# design.net
KiCad netlist of a schematic drawn in Altium Designer
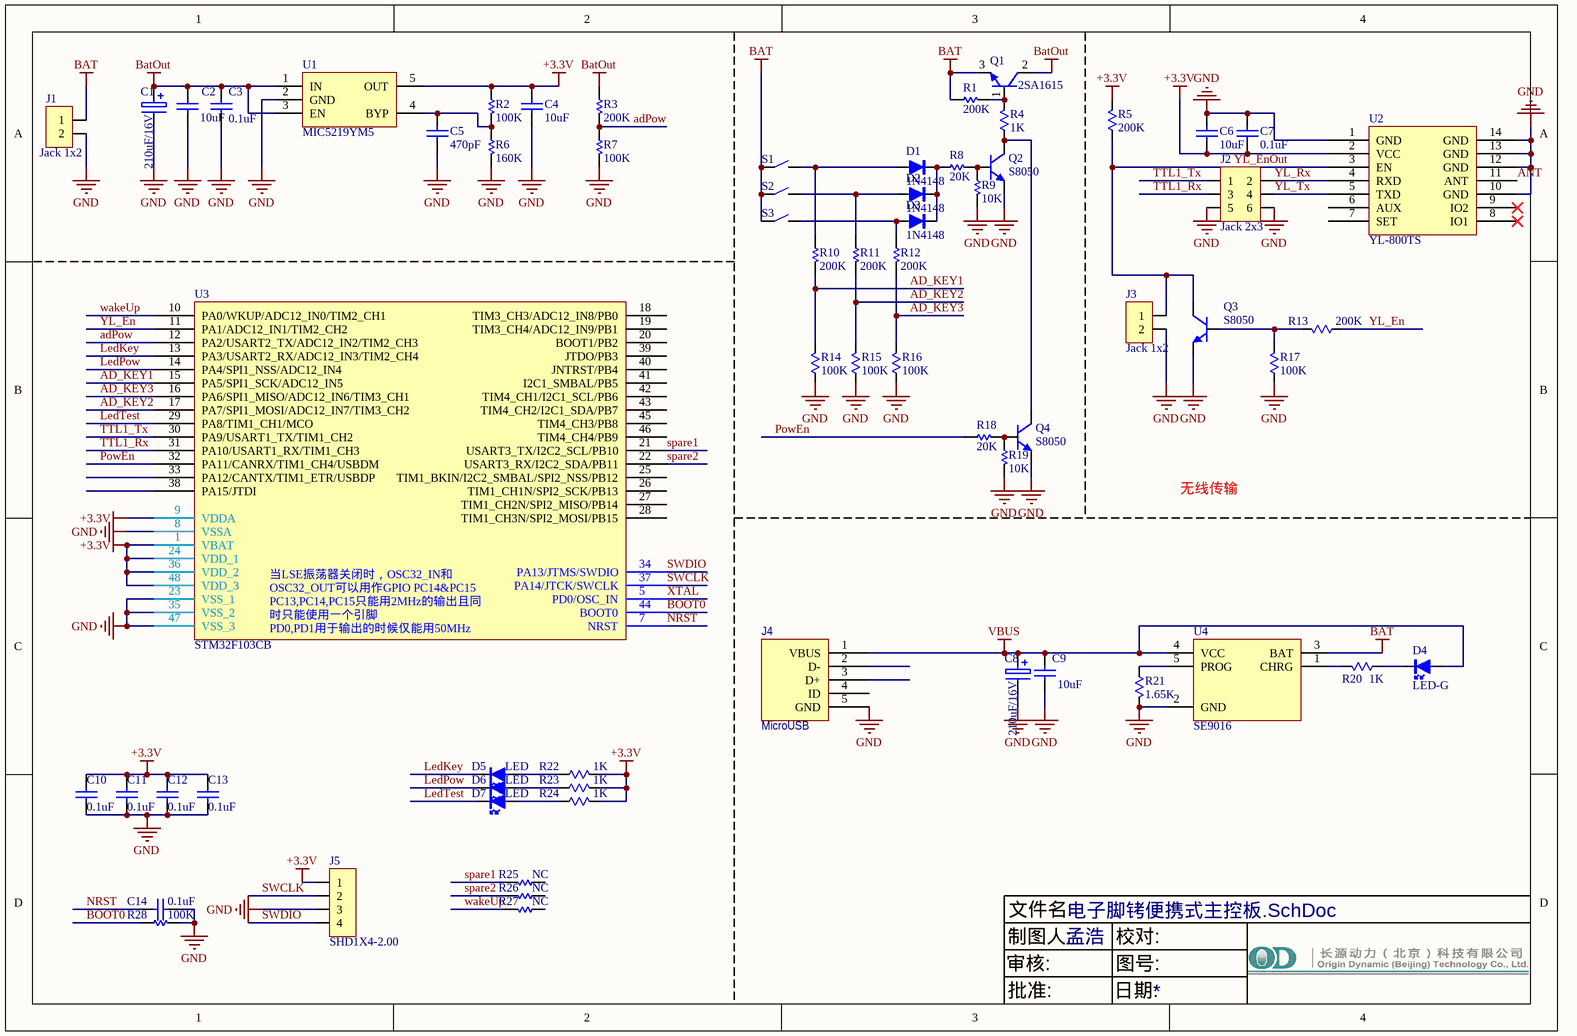
[diagram p0: 电子脚铐便携式主控板.SchDoc]

(export (version "E")
  (design (tool "Eeschema 10.0.6"))
  (components
    (comp (ref "C1") (value "210uF/16V") (footprint "C7343") (libsource (lib "RLCYDF") (part "Cap Poll")))
    (comp (ref "C2")
      (value "10uF")
      (footprint "C0603")
      (description "CAP")
      (fields (field (name "PUBLISHER") "Altium Limited"))
      (libsource (lib "Passive Components Class") (part "CAP"))
    )
    (comp (ref "C3") (value "0.1uF") (footprint "C0603") (libsource (lib "RLCYDF") (part "Cap Semi")))
    (comp (ref "C4")
      (value "10uF")
      (footprint "C0603")
      (description "CAP")
      (fields (field (name "PUBLISHER") "Altium Limited"))
      (libsource (lib "Passive Components Class") (part "CAP"))
    )
    (comp (ref "C5")
      (value "470pF")
      (footprint "C0603")
      (description "CAP")
      (fields (field (name "PUBLISHER") "Altium Limited"))
      (libsource (lib "Passive Components Class") (part "CAP"))
    )
    (comp (ref "C6")
      (value "10uF")
      (footprint "C0603")
      (description "CAP")
      (fields (field (name "PUBLISHER") "Altium Limited"))
      (libsource (lib "Passive Components Class") (part "CAP"))
    )
    (comp (ref "C7")
      (value "0.1uF")
      (footprint "C0603")
      (description "CAP")
      (fields (field (name "PUBLISHER") "Altium Limited"))
      (libsource (lib "Passive Components Class") (part "CAP"))
    )
    (comp (ref "C8") (value "210uF/16V") (footprint "C7343") (libsource (lib "RLCYDF") (part "Cap Poll")))
    (comp (ref "C9")
      (value "10uF")
      (footprint "C0603")
      (description "Capacitor")
      (fields (field (name "Comment") "Cap") (field (name "PUBLISHER") "Altium Limited"))
      (libsource (lib "Miscellaneous Devices") (part "Cap"))
    )
    (comp (ref "C10") (value "0.1uF") (footprint "C0603") (libsource (lib "RLCYDF") (part "Cap Semi")))
    (comp (ref "C11") (value "0.1uF") (footprint "C0603") (libsource (lib "RLCYDF") (part "Cap Semi")))
    (comp (ref "C12") (value "0.1uF") (footprint "C0603") (libsource (lib "RLCYDF") (part "Cap Semi")))
    (comp (ref "C13") (value "0.1uF") (footprint "C0603") (libsource (lib "RLCYDF") (part "Cap Semi")))
    (comp (ref "C14") (value "0.1uF") (footprint "C0603") (libsource (lib "RLCYDF") (part "Cap Semi")))
    (comp (ref "D1")
      (value "1N4148")
      (footprint "SOD-80-S")
      (description "Silicon Epitaxial Planar Diodes")
      (libsource (lib "Passive Components Class") (part "DIODE-SWITCHING"))
    )
    (comp (ref "D2")
      (value "1N4148")
      (footprint "SOD-80-S")
      (description "Silicon Epitaxial Planar Diodes")
      (libsource (lib "Passive Components Class") (part "DIODE-SWITCHING"))
    )
    (comp (ref "D3")
      (value "1N4148")
      (footprint "SOD-80-S")
      (description "Silicon Epitaxial Planar Diodes")
      (libsource (lib "Passive Components Class") (part "DIODE-SWITCHING"))
    )
    (comp (ref "D4")
      (value "LED-G")
      (footprint "LED0805")
      (libsource (lib "Passive Components Class") (part "LED"))
    )
    (comp (ref "D5")
      (value "LED")
      (footprint "LED0805")
      (libsource (lib "Passive Components Class") (part "LED"))
    )
    (comp (ref "D6")
      (value "LED")
      (footprint "LED0805")
      (libsource (lib "Passive Components Class") (part "LED"))
    )
    (comp (ref "D7")
      (value "LED")
      (footprint "LED0805")
      (libsource (lib "Passive Components Class") (part "LED"))
    )
    (comp (ref "J1")
      (value "Jack 1x2")
      (footprint "DF13-2P-1.25V")
      (description "插座")
      (libsource (lib "Connector") (part "Jack 1x2"))
    )
    (comp (ref "J2")
      (value "Jack 2x3")
      (footprint "Jk2*3-2.0")
      (description "双排座")
      (libsource (lib "Connector") (part "Jack 2x3"))
    )
    (comp (ref "J3")
      (value "Jack 1x2")
      (footprint "A6S-1101-PH")
      (description "插座")
      (libsource (lib "Connector") (part "Jack 1x2"))
    )
    (comp (ref "J4") (value "MicroUSB") (footprint "MICRO-USB") (libsource (lib "JLib") (part "MicroUSB")))
    (comp (ref "J5")
      (value "SHD1X4-2.00")
      (footprint "Jk1*4-2.0")
      (libsource (lib "Connector Class") (part "HEADER1X4"))
    )
    (comp (ref "Q1") (value "2SA1615") (footprint "TO-252") (libsource (lib "ArmArmor") (part "MJD122")))
    (comp (ref "Q2")
      (value "S8050")
      (footprint "SOT-23")
      (description "NPN triode, 0.5A Max")
      (libsource (lib "RLCYDF") (part "S8050"))
    )
    (comp (ref "Q3")
      (value "S8050")
      (footprint "SOT-23")
      (description "NPN triode, 0.5A Max")
      (libsource (lib "RLCYDF") (part "S8050"))
    )
    (comp (ref "Q4")
      (value "S8050")
      (footprint "SOT-23")
      (description "NPN triode, 0.5A Max")
      (libsource (lib "RLCYDF") (part "S8050"))
    )
    (comp (ref "R1") (value "200K") (footprint "R0603") (libsource (lib "RLCYDF") (part "Res")))
    (comp (ref "R2") (value "100K") (footprint "R0603") (libsource (lib "RLCYDF") (part "Res")))
    (comp (ref "R3") (value "200K") (footprint "R0603") (libsource (lib "RLCYDF") (part "Res")))
    (comp (ref "R4")
      (value "1K")
      (footprint "R0603")
      (description "Resistor")
      (fields (field (name "PUBLISHER") "Altium Limited"))
      (libsource (lib "Passive Components Class") (part "RES"))
    )
    (comp (ref "R5")
      (value "200K")
      (footprint "R0603")
      (description "Resistor")
      (fields (field (name "PUBLISHER") "Altium Limited"))
      (libsource (lib "Passive Components Class") (part "RES"))
    )
    (comp (ref "R6") (value "160K") (footprint "R0603") (libsource (lib "RLCYDF") (part "Res")))
    (comp (ref "R7") (value "100K") (footprint "R0603") (libsource (lib "RLCYDF") (part "Res")))
    (comp (ref "R8") (value "20K") (footprint "R0603") (libsource (lib "RLCYDF") (part "Res")))
    (comp (ref "R9") (value "10K") (footprint "R0603") (libsource (lib "RLCYDF") (part "Res")))
    (comp (ref "R10") (value "200K") (footprint "R0603") (libsource (lib "RLCYDF") (part "Res")))
    (comp (ref "R11") (value "200K") (footprint "R0603") (libsource (lib "RLCYDF") (part "Res")))
    (comp (ref "R12") (value "200K") (footprint "R0603") (libsource (lib "RLCYDF") (part "Res")))
    (comp (ref "R13")
      (value "200K")
      (footprint "R0603")
      (description "Resistor")
      (fields (field (name "PUBLISHER") "Altium Limited"))
      (libsource (lib "Passive Components Class") (part "RES"))
    )
    (comp (ref "R14")
      (value "100K")
      (footprint "R0603")
      (description "Resistor")
      (fields (field (name "PUBLISHER") "Altium Limited"))
      (libsource (lib "Passive Components Class") (part "RES"))
    )
    (comp (ref "R15")
      (value "100K")
      (footprint "R0603")
      (description "Resistor")
      (fields (field (name "PUBLISHER") "Altium Limited"))
      (libsource (lib "Passive Components Class") (part "RES"))
    )
    (comp (ref "R16")
      (value "100K")
      (footprint "R0603")
      (description "Resistor")
      (fields (field (name "PUBLISHER") "Altium Limited"))
      (libsource (lib "Passive Components Class") (part "RES"))
    )
    (comp (ref "R17")
      (value "100K")
      (footprint "R0603")
      (description "Resistor")
      (fields (field (name "PUBLISHER") "Altium Limited"))
      (libsource (lib "Passive Components Class") (part "RES"))
    )
    (comp (ref "R18") (value "20K") (footprint "R0603") (libsource (lib "RLCYDF") (part "Res")))
    (comp (ref "R19") (value "10K") (footprint "R0603") (libsource (lib "RLCYDF") (part "Res")))
    (comp (ref "R20")
      (value "1K")
      (footprint "R0603")
      (description "Resistor")
      (fields (field (name "PUBLISHER") "Altium Limited"))
      (libsource (lib "UP-Robot") (part "Res"))
    )
    (comp (ref "R21")
      (value "1.65K")
      (footprint "R0603")
      (description "Resistor")
      (fields (field (name "PUBLISHER") "Altium Limited"))
      (libsource (lib "Temp") (part "Res"))
    )
    (comp (ref "R22")
      (value "1K")
      (footprint "R0603")
      (description "Resistor")
      (fields (field (name "PUBLISHER") "Altium Limited"))
      (libsource (lib "UP-Robot") (part "Res"))
    )
    (comp (ref "R23")
      (value "1K")
      (footprint "R0603")
      (description "Resistor")
      (fields (field (name "PUBLISHER") "Altium Limited"))
      (libsource (lib "UP-Robot") (part "Res"))
    )
    (comp (ref "R24")
      (value "1K")
      (footprint "R0603")
      (description "Resistor")
      (fields (field (name "PUBLISHER") "Altium Limited"))
      (libsource (lib "UP-Robot") (part "Res"))
    )
    (comp (ref "R25") (value "NC") (footprint "R0603") (libsource (lib "RLCYDF") (part "Res")))
    (comp (ref "R26") (value "NC") (footprint "R0603") (libsource (lib "RLCYDF") (part "Res")))
    (comp (ref "R27") (value "NC") (footprint "R0603") (libsource (lib "RLCYDF") (part "Res")))
    (comp (ref "R28") (value "100K") (footprint "R0603") (libsource (lib "RLCYDF") (part "Res")))
    (comp (ref "S1") (value "Switch") (footprint "B3F-4055") (libsource (lib "Connector") (part "Sw")))
    (comp (ref "S2") (value "Switch") (footprint "B3F-4055") (libsource (lib "Connector") (part "Sw")))
    (comp (ref "S3") (value "Switch") (footprint "B3F-4055") (libsource (lib "Connector") (part "Sw")))
    (comp (ref "U1") (value "MIC5219YM5") (footprint "SOT-23-5") (libsource (lib "Power") (part "MIC5205")))
    (comp (ref "U2") (value "YL-800TS") (footprint "YL-800TS") (libsource (lib "Module") (part "YL-800TS")))
    (comp (ref "U3")
      (value "STM32F103CB")
      (footprint "LQFP48")
      (libsource (lib "stm32") (part "STM32F103Cx"))
    )
    (comp (ref "U4") (value "SE9016") (footprint "SOT-23-5") (libsource (lib "chip") (part "SE9016")))
  )
  (nets
    (net (code "1") (name "+3.3V") (class "Default")
      (node (ref "C10") (pin "1") (pinfunction "1_1") (pintype "passive"))
      (node (ref "C11") (pin "1") (pinfunction "1_1") (pintype "passive"))
      (node (ref "C12") (pin "1") (pinfunction "1_1") (pintype "passive"))
      (node (ref "C13") (pin "1") (pinfunction "1_1") (pintype "passive"))
      (node (ref "C4") (pin "1") (pinfunction "1_1") (pintype "passive"))
      (node (ref "C6") (pin "1") (pinfunction "1_1") (pintype "passive"))
      (node (ref "C7") (pin "1") (pinfunction "1_1") (pintype "passive"))
      (node (ref "J5") (pin "1") (pinfunction "1_1") (pintype "passive"))
      (node (ref "R2") (pin "1") (pinfunction "1_1") (pintype "passive"))
      (node (ref "R22") (pin "1") (pinfunction "1_1") (pintype "passive"))
      (node (ref "R23") (pin "1") (pinfunction "1_1") (pintype "passive"))
      (node (ref "R24") (pin "1") (pinfunction "1_1") (pintype "passive"))
      (node (ref "R5") (pin "2") (pinfunction "2_2") (pintype "passive"))
      (node (ref "U1") (pin "5") (pinfunction "OUT_5") (pintype "passive"))
      (node (ref "U2") (pin "2") (pinfunction "VCC_2") (pintype "passive"))
      (node (ref "U3") (pin "1") (pinfunction "VBAT_1") (pintype "power_in"))
      (node (ref "U3") (pin "24") (pinfunction "VDD_1_24") (pintype "power_in"))
      (node (ref "U3") (pin "36") (pinfunction "VDD_2_36") (pintype "power_in"))
      (node (ref "U3") (pin "48") (pinfunction "VDD_3_48") (pintype "power_in"))
      (node (ref "U3") (pin "9") (pinfunction "VDDA_9") (pintype "power_in"))
    )
    (net (code "2") (name "/AD_KEY1") (class "Default")
      (node (ref "R10") (pin "2") (pinfunction "2_2") (pintype "passive"))
      (node (ref "R14") (pin "2") (pinfunction "2_2") (pintype "passive"))
      (node (ref "U3") (pin "15") (pinfunction "PA5/SPI1_SCK/ADC12_IN5_15") (pintype "passive"))
    )
    (net (code "3") (name "/AD_KEY2") (class "Default")
      (node (ref "R11") (pin "2") (pinfunction "2_2") (pintype "passive"))
      (node (ref "R15") (pin "2") (pinfunction "2_2") (pintype "passive"))
      (node (ref "U3") (pin "17") (pinfunction "PA7/SPI1_MOSI/ADC12_IN7/TIM3_CH2_17") (pintype "passive"))
    )
    (net (code "4") (name "/AD_KEY3") (class "Default")
      (node (ref "R12") (pin "2") (pinfunction "2_2") (pintype "passive"))
      (node (ref "R16") (pin "2") (pinfunction "2_2") (pintype "passive"))
      (node (ref "U3") (pin "16") (pinfunction "PA6/SPI1_MISO/ADC12_IN6/TIM3_CH1_16") (pintype "passive"))
    )
    (net (code "5") (name "/ANT") (class "Default")
      (node (ref "U2") (pin "11") (pinfunction "ANT_11") (pintype "passive"))
    )
    (net (code "6") (name "/BOOT0") (class "Default")
      (node (ref "R28") (pin "1") (pinfunction "1_1") (pintype "passive"))
      (node (ref "U3") (pin "44") (pinfunction "BOOT0_44") (pintype "passive"))
    )
    (net (code "7") (name "/LedKey") (class "Default")
      (node (ref "D5") (pin "2") (pinfunction "K_2") (pintype "passive"))
      (node (ref "U3") (pin "13") (pinfunction "PA3/USART2_RX/ADC12_IN3/TIM2_CH4_13") (pintype "passive"))
    )
    (net (code "8") (name "/LedPow") (class "Default")
      (node (ref "D6") (pin "2") (pinfunction "K_2") (pintype "passive"))
      (node (ref "U3") (pin "14") (pinfunction "PA4/SPI1_NSS/ADC12_IN4_14") (pintype "passive"))
    )
    (net (code "9") (name "/LedTest") (class "Default")
      (node (ref "D7") (pin "2") (pinfunction "K_2") (pintype "passive"))
      (node (ref "U3") (pin "29") (pinfunction "PA8/TIM1_CH1/MCO_29") (pintype "passive"))
    )
    (net (code "10") (name "/NRST") (class "Default")
      (node (ref "C14") (pin "1") (pinfunction "1_1") (pintype "passive"))
      (node (ref "U3") (pin "7") (pinfunction "NRST_7") (pintype "passive"))
    )
    (net (code "11") (name "/PowEn") (class "Default")
      (node (ref "R18") (pin "1") (pinfunction "1_1") (pintype "passive"))
      (node (ref "U3") (pin "32") (pinfunction "PA11/CANRX/TIM1_CH4/USBDM_32") (pintype "passive"))
    )
    (net (code "12") (name "/SWCLK") (class "Default")
      (node (ref "J5") (pin "2") (pinfunction "2_2") (pintype "passive"))
      (node (ref "U3") (pin "37") (pinfunction "PA14/JTCK/SWCLK_37") (pintype "passive"))
    )
    (net (code "13") (name "/SWDIO") (class "Default")
      (node (ref "J5") (pin "4") (pinfunction "4_4") (pintype "passive"))
      (node (ref "U3") (pin "34") (pinfunction "PA13/JTMS/SWDIO_34") (pintype "passive"))
    )
    (net (code "14") (name "/TTL1_Rx") (class "Default")
      (node (ref "J2") (pin "3") (pinfunction "3_3") (pintype "passive"))
      (node (ref "U3") (pin "31") (pinfunction "PA10/USART1_RX/TIM1_CH3_31") (pintype "passive"))
    )
    (net (code "15") (name "/TTL1_Tx") (class "Default")
      (node (ref "J2") (pin "1") (pinfunction "1_1") (pintype "passive"))
      (node (ref "U3") (pin "30") (pinfunction "PA9/USART1_TX/TIM1_CH2_30") (pintype "passive"))
    )
    (net (code "16") (name "/XTAL") (class "Default")
      (node (ref "U3") (pin "5") (pinfunction "PD0/OSC_IN_5") (pintype "passive"))
    )
    (net (code "17") (name "/YL_En") (class "Default")
      (node (ref "R13") (pin "1") (pinfunction "1_1") (pintype "passive"))
      (node (ref "U3") (pin "11") (pinfunction "PA1/ADC12_IN1/TIM2_CH2_11") (pintype "passive"))
    )
    (net (code "18") (name "/YL_EnOut") (class "Default")
      (node (ref "J3") (pin "1") (pinfunction "1_1") (pintype "passive"))
      (node (ref "Q3") (pin "3") (pinfunction "c_3") (pintype "passive"))
      (node (ref "R5") (pin "1") (pinfunction "1_1") (pintype "passive"))
      (node (ref "U2") (pin "3") (pinfunction "EN_3") (pintype "passive"))
    )
    (net (code "19") (name "/YL_Rx") (class "Default")
      (node (ref "J2") (pin "2") (pinfunction "2_2") (pintype "passive"))
      (node (ref "U2") (pin "4") (pinfunction "RXD_4") (pintype "passive"))
    )
    (net (code "20") (name "/YL_Tx") (class "Default")
      (node (ref "J2") (pin "4") (pinfunction "4_4") (pintype "passive"))
      (node (ref "U2") (pin "5") (pinfunction "TXD_5") (pintype "passive"))
    )
    (net (code "21") (name "/adPow") (class "Default")
      (node (ref "R3") (pin "2") (pinfunction "2_2") (pintype "passive"))
      (node (ref "R7") (pin "1") (pinfunction "1_1") (pintype "passive"))
      (node (ref "U3") (pin "12") (pinfunction "PA2/USART2_TX/ADC12_IN2/TIM2_CH3_12") (pintype "passive"))
    )
    (net (code "22") (name "/spare1") (class "Default")
      (node (ref "R25") (pin "2") (pinfunction "2_2") (pintype "passive"))
      (node (ref "U3") (pin "21") (pinfunction "USART3_TX/I2C2_SCL/PB10_21") (pintype "passive"))
    )
    (net (code "23") (name "/spare2") (class "Default")
      (node (ref "R26") (pin "2") (pinfunction "2_2") (pintype "passive"))
      (node (ref "U3") (pin "22") (pinfunction "USART3_RX/I2C2_SDA/PB11_22") (pintype "passive"))
    )
    (net (code "24") (name "/wakeUp") (class "Default")
      (node (ref "R27") (pin "2") (pinfunction "2_2") (pintype "passive"))
      (node (ref "U3") (pin "10") (pinfunction "PA0/WKUP/ADC12_IN0/TIM2_CH1_10") (pintype "passive"))
    )
    (net (code "25") (name "BAT") (class "Default")
      (node (ref "J1") (pin "1") (pinfunction "1_1") (pintype "passive"))
      (node (ref "Q1") (pin "3") (pinfunction "E_3") (pintype "passive"))
      (node (ref "R1") (pin "1") (pinfunction "1_1") (pintype "passive"))
      (node (ref "S1") (pin "1") (pinfunction "1_1") (pintype "passive"))
      (node (ref "S2") (pin "1") (pinfunction "1_1") (pintype "passive"))
      (node (ref "S3") (pin "1") (pinfunction "1_1") (pintype "passive"))
      (node (ref "U4") (pin "3") (pinfunction "BAT_3") (pintype "passive"))
    )
    (net (code "26") (name "BatOut") (class "Default")
      (node (ref "C1") (pin "1") (pinfunction "1_1") (pintype "passive"))
      (node (ref "C2") (pin "1") (pinfunction "1_1") (pintype "passive"))
      (node (ref "C3") (pin "2") (pinfunction "2_2") (pintype "passive"))
      (node (ref "Q1") (pin "2") (pinfunction "C_2") (pintype "passive"))
      (node (ref "R3") (pin "1") (pinfunction "1_1") (pintype "passive"))
      (node (ref "U1") (pin "1") (pinfunction "IN_1") (pintype "passive"))
      (node (ref "U1") (pin "3") (pinfunction "EN_3") (pintype "passive"))
    )
    (net (code "27") (name "GND") (class "Default")
      (node (ref "C1") (pin "2") (pinfunction "2_2") (pintype "passive"))
      (node (ref "C10") (pin "2") (pinfunction "2_2") (pintype "passive"))
      (node (ref "C11") (pin "2") (pinfunction "2_2") (pintype "passive"))
      (node (ref "C12") (pin "2") (pinfunction "2_2") (pintype "passive"))
      (node (ref "C13") (pin "2") (pinfunction "2_2") (pintype "passive"))
      (node (ref "C14") (pin "2") (pinfunction "2_2") (pintype "passive"))
      (node (ref "C2") (pin "2") (pinfunction "2_2") (pintype "passive"))
      (node (ref "C3") (pin "1") (pinfunction "1_1") (pintype "passive"))
      (node (ref "C4") (pin "2") (pinfunction "2_2") (pintype "passive"))
      (node (ref "C5") (pin "2") (pinfunction "2_2") (pintype "passive"))
      (node (ref "C6") (pin "2") (pinfunction "2_2") (pintype "passive"))
      (node (ref "C7") (pin "2") (pinfunction "2_2") (pintype "passive"))
      (node (ref "C8") (pin "2") (pinfunction "2_2") (pintype "passive"))
      (node (ref "C9") (pin "2") (pinfunction "2_2") (pintype "passive"))
      (node (ref "J1") (pin "2") (pinfunction "2_2") (pintype "passive"))
      (node (ref "J2") (pin "5") (pinfunction "5_5") (pintype "passive"))
      (node (ref "J2") (pin "6") (pinfunction "6_6") (pintype "passive"))
      (node (ref "J3") (pin "2") (pinfunction "2_2") (pintype "passive"))
      (node (ref "J4") (pin "5") (pinfunction "GND_5") (pintype "passive"))
      (node (ref "J5") (pin "3") (pinfunction "3_3") (pintype "passive"))
      (node (ref "Q2") (pin "2") (pinfunction "e_2") (pintype "passive"))
      (node (ref "Q3") (pin "2") (pinfunction "e_2") (pintype "passive"))
      (node (ref "Q4") (pin "2") (pinfunction "e_2") (pintype "passive"))
      (node (ref "R14") (pin "1") (pinfunction "1_1") (pintype "passive"))
      (node (ref "R15") (pin "1") (pinfunction "1_1") (pintype "passive"))
      (node (ref "R16") (pin "1") (pinfunction "1_1") (pintype "passive"))
      (node (ref "R17") (pin "1") (pinfunction "1_1") (pintype "passive"))
      (node (ref "R19") (pin "2") (pinfunction "2_2") (pintype "passive"))
      (node (ref "R21") (pin "1") (pinfunction "1_1") (pintype "passive"))
      (node (ref "R28") (pin "2") (pinfunction "2_2") (pintype "passive"))
      (node (ref "R6") (pin "2") (pinfunction "2_2") (pintype "passive"))
      (node (ref "R7") (pin "2") (pinfunction "2_2") (pintype "passive"))
      (node (ref "R9") (pin "2") (pinfunction "2_2") (pintype "passive"))
      (node (ref "U1") (pin "2") (pinfunction "GND_2") (pintype "passive"))
      (node (ref "U2") (pin "1") (pinfunction "GND_1") (pintype "passive"))
      (node (ref "U2") (pin "10") (pinfunction "GND_10") (pintype "passive"))
      (node (ref "U2") (pin "12") (pinfunction "GND_12") (pintype "passive"))
      (node (ref "U2") (pin "13") (pinfunction "GND_13") (pintype "passive"))
      (node (ref "U2") (pin "14") (pinfunction "GND_14") (pintype "passive"))
      (node (ref "U3") (pin "23") (pinfunction "VSS_1_23") (pintype "power_in"))
      (node (ref "U3") (pin "35") (pinfunction "VSS_2_35") (pintype "power_in"))
      (node (ref "U3") (pin "47") (pinfunction "VSS_3_47") (pintype "power_in"))
      (node (ref "U3") (pin "8") (pinfunction "VSSA_8") (pintype "power_in"))
      (node (ref "U4") (pin "2") (pinfunction "GND_2") (pintype "passive"))
    )
    (net (code "28") (name "Net-(D1-A)") (class "Default")
      (node (ref "D1") (pin "1") (pinfunction "A_1") (pintype "passive"))
      (node (ref "R10") (pin "1") (pinfunction "1_1") (pintype "passive"))
      (node (ref "S1") (pin "2") (pinfunction "2_2") (pintype "passive"))
    )
    (net (code "29") (name "Net-(D1-K)") (class "Default")
      (node (ref "D1") (pin "2") (pinfunction "K_2") (pintype "passive"))
      (node (ref "D2") (pin "2") (pinfunction "K_2") (pintype "passive"))
      (node (ref "D3") (pin "2") (pinfunction "K_2") (pintype "passive"))
      (node (ref "R8") (pin "1") (pinfunction "1_1") (pintype "passive"))
    )
    (net (code "30") (name "Net-(D2-A)") (class "Default")
      (node (ref "D2") (pin "1") (pinfunction "A_1") (pintype "passive"))
      (node (ref "R11") (pin "1") (pinfunction "1_1") (pintype "passive"))
      (node (ref "S2") (pin "2") (pinfunction "2_2") (pintype "passive"))
    )
    (net (code "31") (name "Net-(D3-A)") (class "Default")
      (node (ref "D3") (pin "1") (pinfunction "A_1") (pintype "passive"))
      (node (ref "R12") (pin "1") (pinfunction "1_1") (pintype "passive"))
      (node (ref "S3") (pin "2") (pinfunction "2_2") (pintype "passive"))
    )
    (net (code "32") (name "Net-(D4-K)") (class "Default")
      (node (ref "D4") (pin "2") (pinfunction "K_2") (pintype "passive"))
      (node (ref "R20") (pin "2") (pinfunction "2_2") (pintype "passive"))
    )
    (net (code "33") (name "Net-(D5-A)") (class "Default")
      (node (ref "D5") (pin "1") (pinfunction "A_1") (pintype "passive"))
      (node (ref "R22") (pin "2") (pinfunction "2_2") (pintype "passive"))
    )
    (net (code "34") (name "Net-(D6-A)") (class "Default")
      (node (ref "D6") (pin "1") (pinfunction "A_1") (pintype "passive"))
      (node (ref "R23") (pin "2") (pinfunction "2_2") (pintype "passive"))
    )
    (net (code "35") (name "Net-(D7-A)") (class "Default")
      (node (ref "D7") (pin "1") (pinfunction "A_1") (pintype "passive"))
      (node (ref "R24") (pin "2") (pinfunction "2_2") (pintype "passive"))
    )
    (net (code "36") (name "Net-(Q1-B)") (class "Default")
      (node (ref "Q1") (pin "1") (pinfunction "B_1") (pintype "passive"))
      (node (ref "R1") (pin "2") (pinfunction "2_2") (pintype "passive"))
      (node (ref "R4") (pin "2") (pinfunction "2_2") (pintype "passive"))
    )
    (net (code "37") (name "Net-(Q2-b)") (class "Default")
      (node (ref "Q2") (pin "1") (pinfunction "b_1") (pintype "passive"))
      (node (ref "R8") (pin "2") (pinfunction "2_2") (pintype "passive"))
      (node (ref "R9") (pin "1") (pinfunction "1_1") (pintype "passive"))
    )
    (net (code "38") (name "Net-(Q2-c)") (class "Default")
      (node (ref "Q2") (pin "3") (pinfunction "c_3") (pintype "passive"))
      (node (ref "Q4") (pin "3") (pinfunction "c_3") (pintype "passive"))
      (node (ref "R4") (pin "1") (pinfunction "1_1") (pintype "passive"))
    )
    (net (code "39") (name "Net-(Q3-b)") (class "Default")
      (node (ref "Q3") (pin "1") (pinfunction "b_1") (pintype "passive"))
      (node (ref "R13") (pin "2") (pinfunction "2_2") (pintype "passive"))
      (node (ref "R17") (pin "2") (pinfunction "2_2") (pintype "passive"))
    )
    (net (code "40") (name "Net-(Q4-b)") (class "Default")
      (node (ref "Q4") (pin "1") (pinfunction "b_1") (pintype "passive"))
      (node (ref "R18") (pin "2") (pinfunction "2_2") (pintype "passive"))
      (node (ref "R19") (pin "1") (pinfunction "1_1") (pintype "passive"))
    )
    (net (code "41") (name "Net-(U1-BYP)") (class "Default")
      (node (ref "C5") (pin "1") (pinfunction "1_1") (pintype "passive"))
      (node (ref "R2") (pin "2") (pinfunction "2_2") (pintype "passive"))
      (node (ref "R6") (pin "1") (pinfunction "1_1") (pintype "passive"))
      (node (ref "U1") (pin "4") (pinfunction "BYP_4") (pintype "passive"))
    )
    (net (code "42") (name "Net-(U4-CHRG)") (class "Default")
      (node (ref "R20") (pin "1") (pinfunction "1_1") (pintype "passive"))
      (node (ref "U4") (pin "1") (pinfunction "CHRG_1") (pintype "passive"))
    )
    (net (code "43") (name "Net-(U4-PROG)") (class "Default")
      (node (ref "R21") (pin "2") (pinfunction "2_2") (pintype "passive"))
      (node (ref "U4") (pin "5") (pinfunction "PROG_5") (pintype "passive"))
    )
    (net (code "44") (name "VBUS") (class "Default")
      (node (ref "C8") (pin "1") (pinfunction "1_1") (pintype "passive"))
      (node (ref "C9") (pin "1") (pinfunction "1_1") (pintype "passive"))
      (node (ref "D4") (pin "1") (pinfunction "A_1") (pintype "passive"))
      (node (ref "J4") (pin "1") (pinfunction "VBUS_1") (pintype "passive"))
      (node (ref "U4") (pin "4") (pinfunction "VCC_4") (pintype "passive"))
    )
    (net (code "45") (name "unconnected-(J4-D+-Pad3)") (class "Default")
      (node (ref "J4") (pin "3") (pinfunction "D+_3") (pintype "passive"))
    )
    (net (code "46") (name "unconnected-(J4-D--Pad2)") (class "Default")
      (node (ref "J4") (pin "2") (pinfunction "D-_2") (pintype "passive"))
    )
    (net (code "47") (name "unconnected-(J4-ID-Pad4)") (class "Default")
      (node (ref "J4") (pin "4") (pinfunction "ID_4") (pintype "passive"))
    )
    (net (code "48") (name "unconnected-(R25-Pad1)") (class "Default")
      (node (ref "R25") (pin "1") (pinfunction "1_1") (pintype "passive"))
    )
    (net (code "49") (name "unconnected-(R26-Pad1)") (class "Default")
      (node (ref "R26") (pin "1") (pinfunction "1_1") (pintype "passive"))
    )
    (net (code "50") (name "unconnected-(R27-Pad1)") (class "Default")
      (node (ref "R27") (pin "1") (pinfunction "1_1") (pintype "passive"))
    )
    (net (code "51") (name "unconnected-(U2-AUX-Pad6)") (class "Default")
      (node (ref "U2") (pin "6") (pinfunction "AUX_6") (pintype "passive"))
    )
    (net (code "52") (name "unconnected-(U2-IO1-Pad8)") (class "Default")
      (node (ref "U2") (pin "8") (pinfunction "IO1_8") (pintype "passive+no_connect"))
    )
    (net (code "53") (name "unconnected-(U2-IO2-Pad9)") (class "Default")
      (node (ref "U2") (pin "9") (pinfunction "IO2_9") (pintype "passive+no_connect"))
    )
    (net (code "54") (name "unconnected-(U2-SET-Pad7)") (class "Default")
      (node (ref "U2") (pin "7") (pinfunction "SET_7") (pintype "passive"))
    )
    (net (code "55") (name "unconnected-(U3-BOOT1{slash}PB2-Pad20)") (class "Default")
      (node (ref "U3") (pin "20") (pinfunction "BOOT1/PB2_20") (pintype "passive"))
    )
    (net (code "56") (name "unconnected-(U3-I2C1_SMBAL{slash}PB5-Pad41)") (class "Default")
      (node (ref "U3") (pin "41") (pinfunction "I2C1_SMBAL/PB5_41") (pintype "passive"))
    )
    (net (code "57") (name "unconnected-(U3-JNTRST{slash}PB4-Pad40)") (class "Default")
      (node (ref "U3") (pin "40") (pinfunction "JNTRST/PB4_40") (pintype "passive"))
    )
    (net (code "58") (name "unconnected-(U3-JTDO{slash}PB3-Pad39)") (class "Default")
      (node (ref "U3") (pin "39") (pinfunction "JTDO/PB3_39") (pintype "passive"))
    )
    (net (code "59") (name "unconnected-(U3-PA12{slash}CANTX{slash}TIM1_ETR{slash}USBDP-Pad33)") (class "Default")
      (node (ref "U3") (pin "33") (pinfunction "PA12/CANTX/TIM1_ETR/USBDP_33") (pintype "passive"))
    )
    (net (code "60") (name "unconnected-(U3-PA15{slash}JTDI-Pad38)") (class "Default")
      (node (ref "U3") (pin "38") (pinfunction "PA15/JTDI_38") (pintype "passive"))
    )
    (net (code "61") (name "unconnected-(U3-PC13-TAMPER-RTC-Pad2)") (class "Default")
      (node (ref "U3") (pin "2") (pinfunction "PC13-TAMPER-RTC_2") (pintype "passive"))
    )
    (net (code "62") (name "unconnected-(U3-PC14-OSC32_IN-Pad3)") (class "Default")
      (node (ref "U3") (pin "3") (pinfunction "PC14-OSC32_IN_3") (pintype "passive"))
    )
    (net (code "63") (name "unconnected-(U3-PC15-OSC32_OUT-Pad4)") (class "Default")
      (node (ref "U3") (pin "4") (pinfunction "PC15-OSC32_OUT_4") (pintype "passive"))
    )
    (net (code "64") (name "unconnected-(U3-PD1{slash}OSC_OUT-Pad6)") (class "Default")
      (node (ref "U3") (pin "6") (pinfunction "PD1/OSC_OUT_6") (pintype "passive"))
    )
    (net (code "65") (name "unconnected-(U3-TIM1_BKIN{slash}I2C2_SMBAL{slash}SPI2_NSS{slash}PB12-Pad25)") (class "Default")
      (node (ref "U3") (pin "25") (pinfunction "TIM1_BKIN/I2C2_SMBAL/SPI2_NSS/PB12_25") (pintype "passive"))
    )
    (net (code "66") (name "unconnected-(U3-TIM1_CH1N{slash}SPI2_SCK{slash}PB13-Pad26)") (class "Default")
      (node (ref "U3") (pin "26") (pinfunction "TIM1_CH1N/SPI2_SCK/PB13_26") (pintype "passive"))
    )
    (net (code "67") (name "unconnected-(U3-TIM1_CH2N{slash}SPI2_MISO{slash}PB14-Pad27)") (class "Default")
      (node (ref "U3") (pin "27") (pinfunction "TIM1_CH2N/SPI2_MISO/PB14_27") (pintype "passive"))
    )
    (net (code "68") (name "unconnected-(U3-TIM1_CH3N{slash}SPI2_MOSI{slash}PB15-Pad28)") (class "Default")
      (node (ref "U3") (pin "28") (pinfunction "TIM1_CH3N/SPI2_MOSI/PB15_28") (pintype "passive"))
    )
    (net (code "69") (name "unconnected-(U3-TIM3_CH3{slash}ADC12_IN8{slash}PB0-Pad18)") (class "Default")
      (node (ref "U3") (pin "18") (pinfunction "TIM3_CH3/ADC12_IN8/PB0_18") (pintype "passive"))
    )
    (net (code "70") (name "unconnected-(U3-TIM3_CH4{slash}ADC12_IN9{slash}PB1-Pad19)") (class "Default")
      (node (ref "U3") (pin "19") (pinfunction "TIM3_CH4/ADC12_IN9/PB1_19") (pintype "passive"))
    )
    (net (code "71") (name "unconnected-(U3-TIM4_CH1{slash}I2C1_SCL{slash}PB6-Pad42)") (class "Default")
      (node (ref "U3") (pin "42") (pinfunction "TIM4_CH1/I2C1_SCL/PB6_42") (pintype "passive"))
    )
    (net (code "72") (name "unconnected-(U3-TIM4_CH2{slash}I2C1_SDA{slash}PB7-Pad43)") (class "Default")
      (node (ref "U3") (pin "43") (pinfunction "TIM4_CH2/I2C1_SDA/PB7_43") (pintype "passive"))
    )
    (net (code "73") (name "unconnected-(U3-TIM4_CH3{slash}PB8-Pad45)") (class "Default")
      (node (ref "U3") (pin "45") (pinfunction "TIM4_CH3/PB8_45") (pintype "passive"))
    )
    (net (code "74") (name "unconnected-(U3-TIM4_CH4{slash}PB9-Pad46)") (class "Default")
      (node (ref "U3") (pin "46") (pinfunction "TIM4_CH4/PB9_46") (pintype "passive"))
    )
  )
)
